# 04B-352.net
KiCad netlist of a schematic drawn in EAGLE
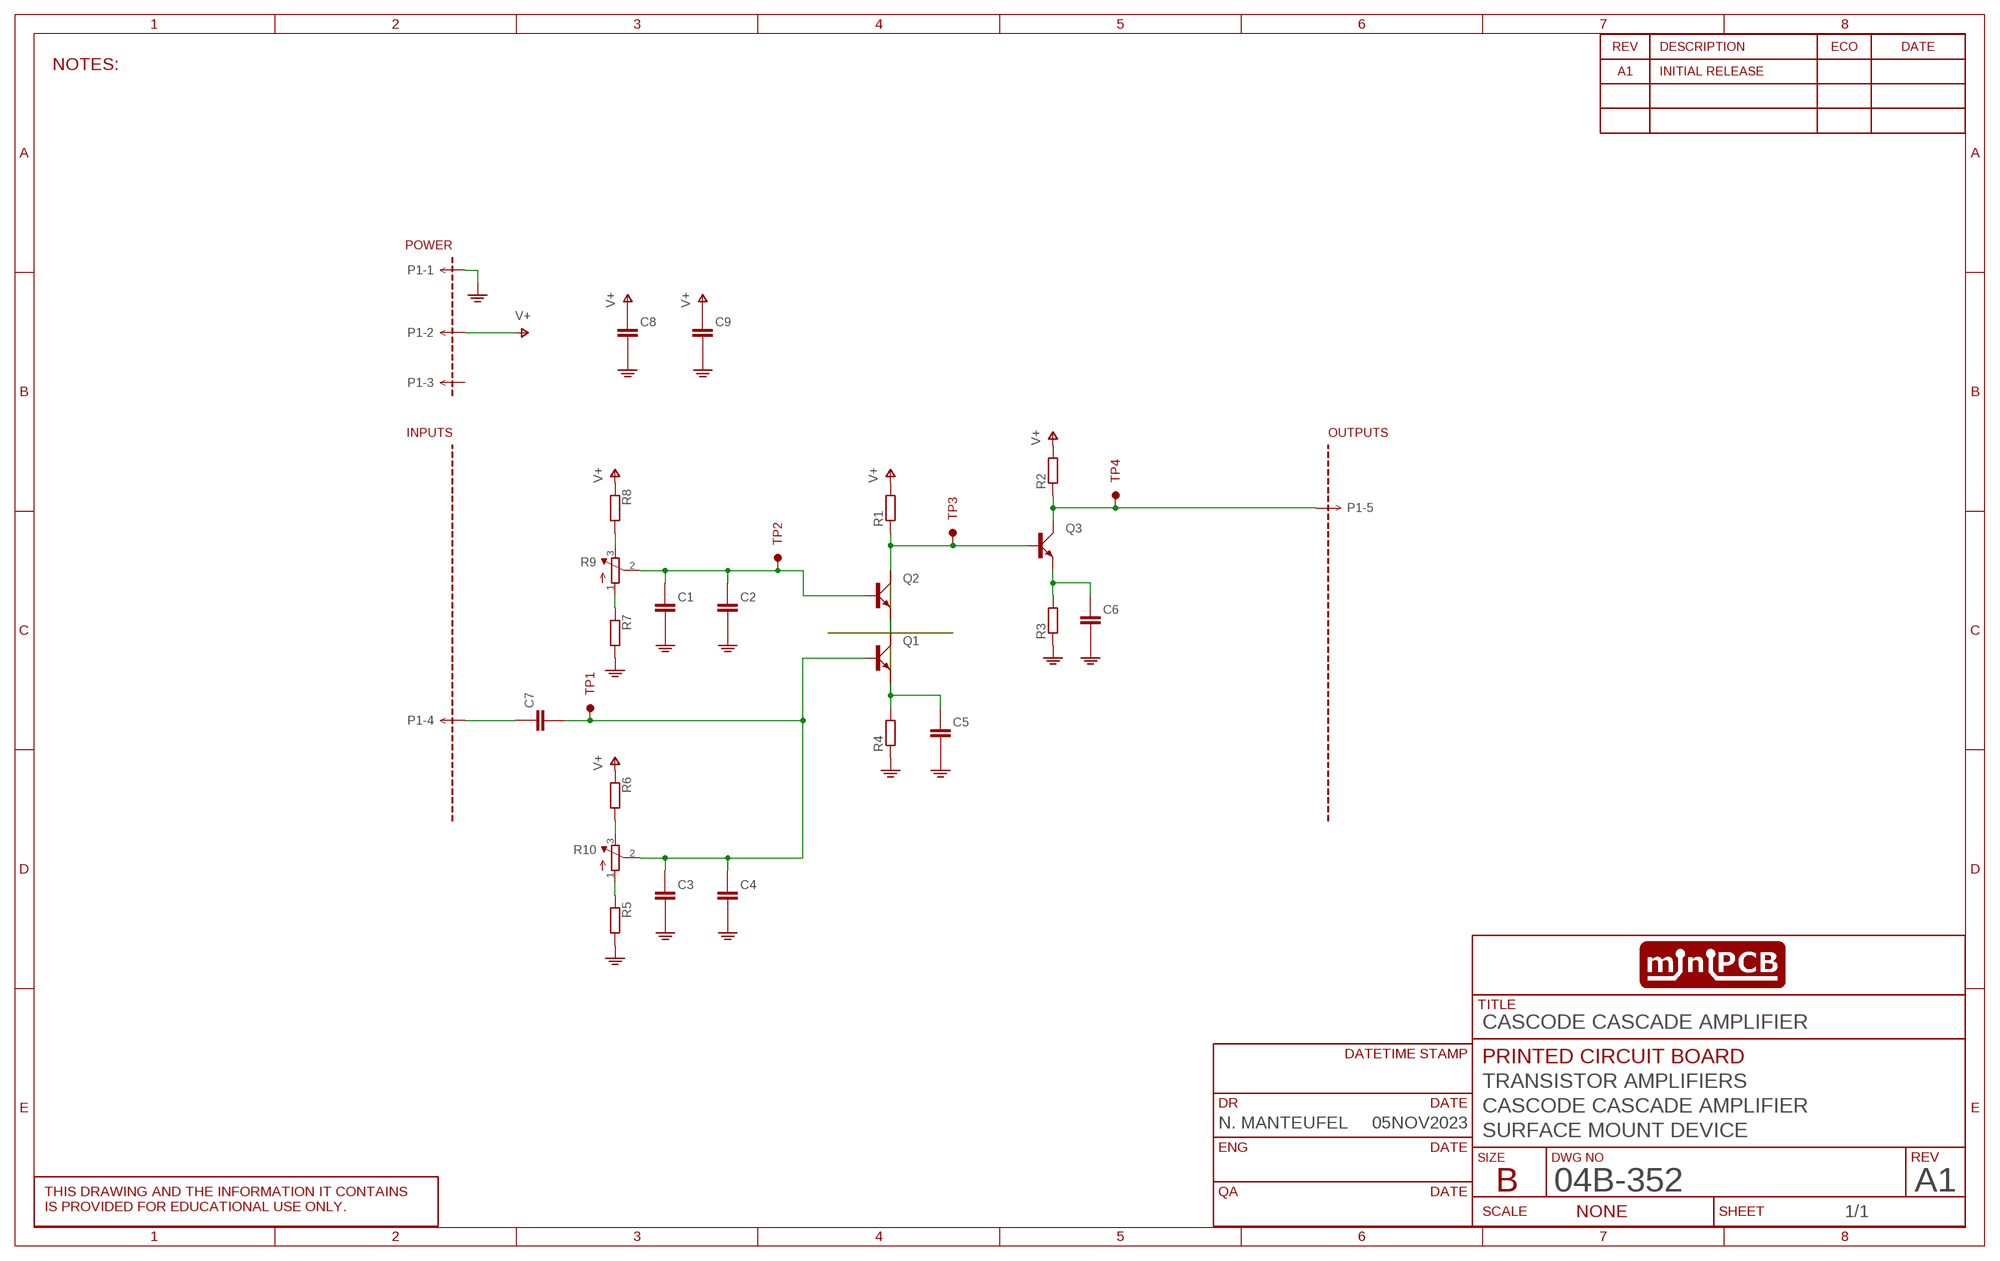
[diagram p0: schematic, sheet 1]

(export (version "E")
  (design (tool "Eeschema 10.0.6"))
  (components
    (comp (ref "C1")
      (value "CAPACITORSMD")
      (footprint "eagle-import:C0805")
      (libsource (lib "eagle-import") (part "CAPACITORSMD"))
    )
    (comp (ref "C2")
      (value "CAPACITORSMD")
      (footprint "eagle-import:C0805")
      (libsource (lib "eagle-import") (part "CAPACITORSMD"))
    )
    (comp (ref "C3")
      (value "CAPACITORSMD")
      (footprint "eagle-import:C0805")
      (libsource (lib "eagle-import") (part "CAPACITORSMD"))
    )
    (comp (ref "C4")
      (value "CAPACITORSMD")
      (footprint "eagle-import:C0805")
      (libsource (lib "eagle-import") (part "CAPACITORSMD"))
    )
    (comp (ref "C5")
      (value "CAPACITORSMD")
      (footprint "eagle-import:C0805")
      (libsource (lib "eagle-import") (part "CAPACITORSMD"))
    )
    (comp (ref "C6")
      (value "CAPACITORSMD")
      (footprint "eagle-import:C0805")
      (libsource (lib "eagle-import") (part "CAPACITORSMD"))
    )
    (comp (ref "C7")
      (value "CAPACITORSMD")
      (footprint "eagle-import:C0805")
      (libsource (lib "eagle-import") (part "CAPACITORSMD"))
    )
    (comp (ref "C8")
      (value "CAPACITORSMD")
      (footprint "eagle-import:C0805")
      (libsource (lib "eagle-import") (part "CAPACITORSMD"))
    )
    (comp (ref "C9")
      (value "CAPACITORSMD")
      (footprint "eagle-import:C0805")
      (libsource (lib "eagle-import") (part "CAPACITORSMD"))
    )
    (comp (ref "P1")
      (value "MINIPCB_5P5P")
      (footprint "eagle-import:PINS_1X5")
      (libsource (lib "eagle-import") (part "MINIPCB_5P5P"))
    )
    (comp (ref "PCB1")
      (value "MINIPCB_0P25X50")
      (footprint "eagle-import:MINIPCB_0P_25X50")
      (fields
        (field (name "PART_NUMBER") "04B-352")
        (field (name "REVISION") "A1-01")
        (field (name "TITLE") "CASCODE CASCADE AMPLIFIERS")
      )
      (libsource (lib "eagle-import") (part "MINIPCB_0P25X50"))
    )
    (comp (ref "Q1")
      (value "BJT_NPNBEC")
      (footprint "eagle-import:SOT23")
      (libsource (lib "eagle-import") (part "BJT_NPNBEC"))
    )
    (comp (ref "Q2")
      (value "BJT_NPNBEC")
      (footprint "eagle-import:SOT23")
      (libsource (lib "eagle-import") (part "BJT_NPNBEC"))
    )
    (comp (ref "Q3")
      (value "BJT_NPNBEC")
      (footprint "eagle-import:SOT23")
      (libsource (lib "eagle-import") (part "BJT_NPNBEC"))
    )
    (comp (ref "R1")
      (value "RESISTORSMD")
      (footprint "eagle-import:R0805")
      (libsource (lib "eagle-import") (part "RESISTORSMD"))
    )
    (comp (ref "R2")
      (value "RESISTORSMD")
      (footprint "eagle-import:R0805")
      (libsource (lib "eagle-import") (part "RESISTORSMD"))
    )
    (comp (ref "R3")
      (value "RESISTORSMD")
      (footprint "eagle-import:R0805")
      (libsource (lib "eagle-import") (part "RESISTORSMD"))
    )
    (comp (ref "R4")
      (value "RESISTORSMD")
      (footprint "eagle-import:R0805")
      (libsource (lib "eagle-import") (part "RESISTORSMD"))
    )
    (comp (ref "R5")
      (value "RESISTORSMD")
      (footprint "eagle-import:R0805")
      (libsource (lib "eagle-import") (part "RESISTORSMD"))
    )
    (comp (ref "R6")
      (value "RESISTORSMD")
      (footprint "eagle-import:R0805")
      (libsource (lib "eagle-import") (part "RESISTORSMD"))
    )
    (comp (ref "R7")
      (value "RESISTORSMD")
      (footprint "eagle-import:R0805")
      (libsource (lib "eagle-import") (part "RESISTORSMD"))
    )
    (comp (ref "R8")
      (value "RESISTORSMD")
      (footprint "eagle-import:R0805")
      (libsource (lib "eagle-import") (part "RESISTORSMD"))
    )
    (comp (ref "R9")
      (value "TRIMPOT0.100THD")
      (footprint "eagle-import:TRIM_0100")
      (libsource (lib "eagle-import") (part "TRIMPOT0.100THD"))
    )
    (comp (ref "R10")
      (value "TRIMPOT0.100THD")
      (footprint "eagle-import:TRIM_0100")
      (libsource (lib "eagle-import") (part "TRIMPOT0.100THD"))
    )
    (comp (ref "TP1")
      (value "TESTPOINTKE5000-SMTEXT")
      (footprint "eagle-import:PINS_1_TESTPOINT_KE5000_NOTEXT")
      (libsource (lib "eagle-import") (part "TESTPOINTKE5000-SMTEXT"))
    )
    (comp (ref "TP2")
      (value "TESTPOINTKE5000-SMTEXT")
      (footprint "eagle-import:PINS_1_TESTPOINT_KE5000_NOTEXT")
      (libsource (lib "eagle-import") (part "TESTPOINTKE5000-SMTEXT"))
    )
    (comp (ref "TP3")
      (value "TESTPOINTKE5000-SMTEXT")
      (footprint "eagle-import:PINS_1_TESTPOINT_KE5000_NOTEXT")
      (libsource (lib "eagle-import") (part "TESTPOINTKE5000-SMTEXT"))
    )
    (comp (ref "TP4")
      (value "TESTPOINTKE5000-SMTEXT")
      (footprint "eagle-import:PINS_1_TESTPOINT_KE5000_NOTEXT")
      (libsource (lib "eagle-import") (part "TESTPOINTKE5000-SMTEXT"))
    )
  )
  (nets
    (net (code "1") (name "GND") (class "Default")
      (node (ref "C1") (pin "2") (pinfunction "-_2") (pintype "passive"))
      (node (ref "C2") (pin "2") (pinfunction "-_2") (pintype "passive"))
      (node (ref "C3") (pin "2") (pinfunction "-_2") (pintype "passive"))
      (node (ref "C4") (pin "2") (pinfunction "-_2") (pintype "passive"))
      (node (ref "C5") (pin "2") (pinfunction "-_2") (pintype "passive"))
      (node (ref "C6") (pin "2") (pinfunction "-_2") (pintype "passive"))
      (node (ref "C8") (pin "2") (pinfunction "-_2") (pintype "passive"))
      (node (ref "C9") (pin "2") (pinfunction "-_2") (pintype "passive"))
      (node (ref "P1") (pin "1") (pinfunction "1_1") (pintype "bidirectional"))
      (node (ref "R3") (pin "1") (pinfunction "1_1") (pintype "passive"))
      (node (ref "R4") (pin "1") (pinfunction "1_1") (pintype "passive"))
      (node (ref "R5") (pin "2") (pinfunction "2_2") (pintype "passive"))
      (node (ref "R7") (pin "2") (pinfunction "2_2") (pintype "passive"))
    )
    (net (code "2") (name "Net-(C1-+)") (class "Default")
      (node (ref "C1") (pin "1") (pinfunction "+_1") (pintype "passive"))
      (node (ref "C2") (pin "1") (pinfunction "+_1") (pintype "passive"))
      (node (ref "Q2") (pin "1") (pinfunction "B_1") (pintype "passive"))
      (node (ref "R9") (pin "2") (pinfunction "S_2") (pintype "passive"))
      (node (ref "TP2") (pin "1") (pinfunction "1_1") (pintype "bidirectional"))
    )
    (net (code "3") (name "Net-(C3-+)") (class "Default")
      (node (ref "C3") (pin "1") (pinfunction "+_1") (pintype "passive"))
      (node (ref "C4") (pin "1") (pinfunction "+_1") (pintype "passive"))
      (node (ref "C7") (pin "2") (pinfunction "-_2") (pintype "passive"))
      (node (ref "Q1") (pin "1") (pinfunction "B_1") (pintype "passive"))
      (node (ref "R10") (pin "2") (pinfunction "S_2") (pintype "passive"))
      (node (ref "TP1") (pin "1") (pinfunction "1_1") (pintype "bidirectional"))
    )
    (net (code "4") (name "Net-(C5-+)") (class "Default")
      (node (ref "C5") (pin "1") (pinfunction "+_1") (pintype "passive"))
      (node (ref "Q1") (pin "2") (pinfunction "E_2") (pintype "passive"))
      (node (ref "R4") (pin "2") (pinfunction "2_2") (pintype "passive"))
    )
    (net (code "5") (name "Net-(C6-+)") (class "Default")
      (node (ref "C6") (pin "1") (pinfunction "+_1") (pintype "passive"))
      (node (ref "Q3") (pin "2") (pinfunction "E_2") (pintype "passive"))
      (node (ref "R3") (pin "2") (pinfunction "2_2") (pintype "passive"))
    )
    (net (code "6") (name "Net-(C7-+)") (class "Default")
      (node (ref "C7") (pin "1") (pinfunction "+_1") (pintype "passive"))
      (node (ref "P1") (pin "4") (pinfunction "1_4") (pintype "bidirectional"))
    )
    (net (code "7") (name "Net-(P1E-1)") (class "Default")
      (node (ref "P1") (pin "5") (pinfunction "1_5") (pintype "bidirectional"))
      (node (ref "Q3") (pin "3") (pinfunction "C_3") (pintype "passive"))
      (node (ref "R2") (pin "1") (pinfunction "1_1") (pintype "passive"))
      (node (ref "TP4") (pin "1") (pinfunction "1_1") (pintype "bidirectional"))
    )
    (net (code "8") (name "Net-(Q1-C)") (class "Default")
      (node (ref "Q1") (pin "3") (pinfunction "C_3") (pintype "passive"))
      (node (ref "Q2") (pin "2") (pinfunction "E_2") (pintype "passive"))
    )
    (net (code "9") (name "Net-(Q2-C)") (class "Default")
      (node (ref "Q2") (pin "3") (pinfunction "C_3") (pintype "passive"))
      (node (ref "Q3") (pin "1") (pinfunction "B_1") (pintype "passive"))
      (node (ref "R1") (pin "1") (pinfunction "1_1") (pintype "passive"))
      (node (ref "TP3") (pin "1") (pinfunction "1_1") (pintype "bidirectional"))
    )
    (net (code "10") (name "Net-(R9-A)") (class "Default")
      (node (ref "R7") (pin "1") (pinfunction "1_1") (pintype "passive"))
      (node (ref "R9") (pin "1") (pinfunction "A_1") (pintype "passive"))
    )
    (net (code "11") (name "Net-(R9-E)") (class "Default")
      (node (ref "R8") (pin "2") (pinfunction "2_2") (pintype "passive"))
      (node (ref "R9") (pin "3") (pinfunction "E_3") (pintype "passive"))
    )
    (net (code "12") (name "Net-(R10-A)") (class "Default")
      (node (ref "R10") (pin "1") (pinfunction "A_1") (pintype "passive"))
      (node (ref "R5") (pin "1") (pinfunction "1_1") (pintype "passive"))
    )
    (net (code "13") (name "Net-(R10-E)") (class "Default")
      (node (ref "R10") (pin "3") (pinfunction "E_3") (pintype "passive"))
      (node (ref "R6") (pin "2") (pinfunction "2_2") (pintype "passive"))
    )
    (net (code "14") (name "V+") (class "Default")
      (node (ref "C8") (pin "1") (pinfunction "+_1") (pintype "passive"))
      (node (ref "C9") (pin "1") (pinfunction "+_1") (pintype "passive"))
      (node (ref "P1") (pin "2") (pinfunction "1_2") (pintype "bidirectional"))
      (node (ref "R1") (pin "2") (pinfunction "2_2") (pintype "passive"))
      (node (ref "R2") (pin "2") (pinfunction "2_2") (pintype "passive"))
      (node (ref "R6") (pin "1") (pinfunction "1_1") (pintype "passive"))
      (node (ref "R8") (pin "1") (pinfunction "1_1") (pintype "passive"))
    )
    (net (code "15") (name "unconnected-(P1C-1-Pad3)") (class "Default")
      (node (ref "P1") (pin "3") (pinfunction "1_3") (pintype "bidirectional"))
    )
  )
)
